# DAC.net
KiCad netlist of a schematic drawn in Altium Designer
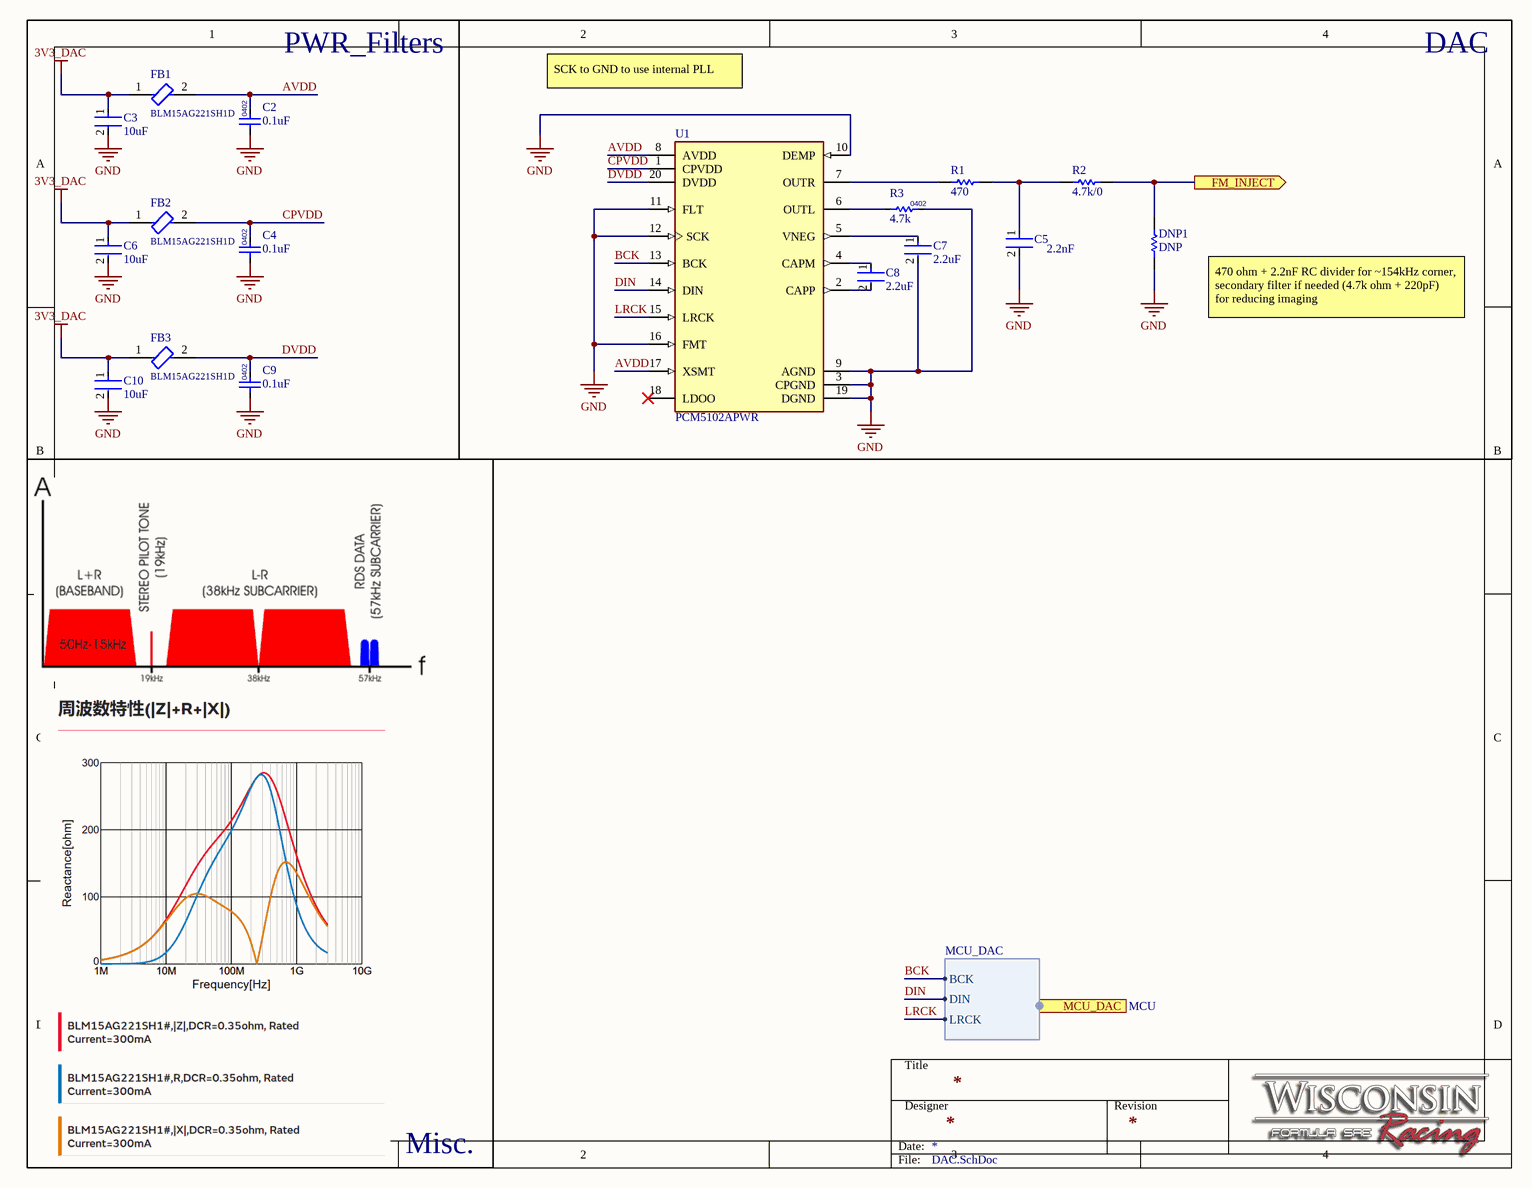
[diagram p0: DAC.SchDoc]

(export (version "E")
  (design (tool "Eeschema 10.0.6"))
  (components
    (comp (ref "C2")
      (value "0.1uF")
      (footprint "FP-CC0402-IPC_B")
      (fields (field (name "TOLERANCE") "10%"))
      (libsource (lib "University of Wisconsin Formula FSAE") (part "0402 ceramic cap"))
    )
    (comp (ref "C3")
      (value "10uF")
      (footprint "FP-GRM155-0_2-IPC_A")
      (description "Chip Multilayer Ceramic Capacitors for General Purpose, 0402, 10uF, X5R, 15%, 20%, 6.3V")
      (libsource (lib "Altium Content Vault") (part "b4654b650e69147ec39a6b967a45e02"))
    )
    (comp (ref "C4")
      (value "0.1uF")
      (footprint "FP-CC0402-IPC_B")
      (fields (field (name "TOLERANCE") "10%"))
      (libsource (lib "University of Wisconsin Formula FSAE") (part "0402 ceramic cap"))
    )
    (comp (ref "C5")
      (value "2.2nF")
      (footprint "FP-GRM155-0_05-IPC_C")
      (description "Chip Multilayer Ceramic Capacitors for General Purpose, 0402, 2200pF, C0G, 30ppm/°C, 5%, 50V")
      (libsource (lib "Altium Content Vault") (part "02cd4be3c70576c341d710602a673aa"))
    )
    (comp (ref "C6")
      (value "10uF")
      (footprint "FP-GRM155-0_2-IPC_A")
      (description "Chip Multilayer Ceramic Capacitors for General Purpose, 0402, 10uF, X5R, 15%, 20%, 6.3V")
      (libsource (lib "Altium Content Vault") (part "b4654b650e69147ec39a6b967a45e02"))
    )
    (comp (ref "C7")
      (value "2.2uF")
      (footprint "FP-GRM155-0_2-IPC_B")
      (description "Chip Multilayer Ceramic Capacitors for General Purpose, 0402, 2.2uF, X7R, 15%, 10%, 10V")
      (libsource (lib "Altium Content Vault") (part "b4654b650e69147ec39a6b967a45e02"))
    )
    (comp (ref "C8")
      (value "2.2uF")
      (footprint "FP-GRM155-0_2-IPC_B")
      (description "Chip Multilayer Ceramic Capacitors for General Purpose, 0402, 2.2uF, X7R, 15%, 10%, 10V")
      (libsource (lib "Altium Content Vault") (part "b4654b650e69147ec39a6b967a45e02"))
    )
    (comp (ref "C9")
      (value "0.1uF")
      (footprint "FP-CC0402-IPC_B")
      (fields (field (name "TOLERANCE") "10%"))
      (libsource (lib "University of Wisconsin Formula FSAE") (part "0402 ceramic cap"))
    )
    (comp (ref "C10")
      (value "10uF")
      (footprint "FP-GRM155-0_2-IPC_A")
      (description "Chip Multilayer Ceramic Capacitors for General Purpose, 0402, 10uF, X5R, 15%, 20%, 6.3V")
      (libsource (lib "Altium Content Vault") (part "b4654b650e69147ec39a6b967a45e02"))
    )
    (comp (ref "DNP1")
      (value "DNP")
      (footprint "RESC1005X40X25NL05T10")
      (fields (field (name "MANUFACTURER") "Yageo / Phycomp") (field (name "PART NUMBER") "RC0402JR-070RL"))
      (libsource (lib "Altium Content Vault") (part "RES"))
    )
    (comp (ref "FB1")
      (value "BLM15AG221SH1D")
      (footprint "FP-BLM15-0_05-MFG")
      (description "Chip Ferrite Bead, 0402, 220Ω @ 100MHz, 0.35Ω, 25%, 300mA")
      (fields (field (name "TOLERANCE") "25%"))
      (libsource (lib "Altium Content Vault") (part "5f30dd21d616792df468990f7003faa"))
    )
    (comp (ref "FB2")
      (value "BLM15AG221SH1D")
      (footprint "FP-BLM15-0_05-MFG")
      (description "Chip Ferrite Bead, 0402, 220Ω @ 100MHz, 0.35Ω, 25%, 300mA")
      (fields (field (name "TOLERANCE") "25%"))
      (libsource (lib "Altium Content Vault") (part "5f30dd21d616792df468990f7003faa"))
    )
    (comp (ref "FB3")
      (value "BLM15AG221SH1D")
      (footprint "FP-BLM15-0_05-MFG")
      (description "Chip Ferrite Bead, 0402, 220Ω @ 100MHz, 0.35Ω, 25%, 300mA")
      (fields (field (name "TOLERANCE") "25%"))
      (libsource (lib "Altium Content Vault") (part "5f30dd21d616792df468990f7003faa"))
    )
    (comp (ref "R1")
      (value "470")
      (footprint "RESC1005X40X25ML05T10")
      (fields (field (name "PART NUMBER") "RC0402FR-07470RL") (field (name "MANUFACTURER") "Yageo / Phycomp"))
      (libsource (lib "Altium Content Vault") (part "RES"))
    )
    (comp (ref "R2")
      (value "4.7k/0")
      (footprint "RESC1005X40X25NL05T10")
      (fields (field (name "MANUFACTURER") "Yageo / Phycomp") (field (name "PART NUMBER") "RC0402JR-070RL"))
      (libsource (lib "Altium Content Vault") (part "RES"))
    )
    (comp (ref "R3")
      (value "4.7k")
      (footprint "RESC1005X40X25NL05T10")
      (description "Res General Purpose Thick Film 0402 4.7K Ohm 1% 1/16W ±100ppm/°C Molded SMD Paper T/R")
      (fields (field (name "TOLERANCE") "1%") (field (name "Comment") "4.7k 1%"))
      (libsource (lib "University of Wisconsin Formula FSAE") (part "RES"))
    )
    (comp (ref "U1")
      (value "PCM5102APWR")
      (footprint "FP-PW0020A-IPC_A")
      (description "IC DAC 16/24/32BIT 384K 20TSSOP")
      (libsource (lib "Altium Content Vault") (part "831166dc95f78e7a0e4986cce343839"))
    )
  )
  (nets
    (net (code "2") (name "/AVDD") (class "Default")
      (node (ref "C2") (pin "2") (pinfunction "2_2") (pintype "passive"))
      (node (ref "FB1") (pin "2") (pinfunction "2_2") (pintype "passive"))
      (node (ref "U1") (pin "17") (pinfunction "XSMT_17") (pintype "input"))
      (node (ref "U1") (pin "8") (pinfunction "AVDD_8") (pintype "power_in"))
    )
    (net (code "3") (name "/BCK") (class "Default")
      (node (ref "U1") (pin "13") (pinfunction "BCK_13") (pintype "input"))
    )
    (net (code "4") (name "/CPVDD") (class "Default")
      (node (ref "C4") (pin "2") (pinfunction "2_2") (pintype "passive"))
      (node (ref "FB2") (pin "2") (pinfunction "2_2") (pintype "passive"))
      (node (ref "U1") (pin "1") (pinfunction "CPVDD_1") (pintype "power_in"))
    )
    (net (code "5") (name "/DIN") (class "Default")
      (node (ref "U1") (pin "14") (pinfunction "DIN_14") (pintype "input"))
    )
    (net (code "6") (name "/DVDD") (class "Default")
      (node (ref "C9") (pin "2") (pinfunction "2_2") (pintype "passive"))
      (node (ref "FB3") (pin "2") (pinfunction "2_2") (pintype "passive"))
      (node (ref "U1") (pin "20") (pinfunction "DVDD_20") (pintype "power_in"))
    )
    (net (code "7") (name "/FM_INJECT") (class "Default")
      (node (ref "DNP1") (pin "2") (pinfunction "2_2") (pintype "passive"))
      (node (ref "R2") (pin "2") (pinfunction "2_2") (pintype "passive"))
    )
    (net (code "8") (name "/LRCK") (class "Default")
      (node (ref "U1") (pin "15") (pinfunction "LRCK_15") (pintype "input"))
    )
    (net (code "10") (name "3V3_DAC") (class "Default")
      (node (ref "C10") (pin "1") (pinfunction "1_1") (pintype "passive"))
      (node (ref "C3") (pin "1") (pinfunction "1_1") (pintype "passive"))
      (node (ref "C6") (pin "1") (pinfunction "1_1") (pintype "passive"))
      (node (ref "FB1") (pin "1") (pinfunction "1_1") (pintype "passive"))
      (node (ref "FB2") (pin "1") (pinfunction "1_1") (pintype "passive"))
      (node (ref "FB3") (pin "1") (pinfunction "1_1") (pintype "passive"))
    )
    (net (code "11") (name "GND") (class "Default")
      (node (ref "C10") (pin "2") (pinfunction "2_2") (pintype "passive"))
      (node (ref "C2") (pin "1") (pinfunction "1_1") (pintype "passive"))
      (node (ref "C3") (pin "2") (pinfunction "2_2") (pintype "passive"))
      (node (ref "C4") (pin "1") (pinfunction "1_1") (pintype "passive"))
      (node (ref "C5") (pin "2") (pinfunction "2_2") (pintype "passive"))
      (node (ref "C6") (pin "2") (pinfunction "2_2") (pintype "passive"))
      (node (ref "C7") (pin "2") (pinfunction "2_2") (pintype "passive"))
      (node (ref "C9") (pin "1") (pinfunction "1_1") (pintype "passive"))
      (node (ref "DNP1") (pin "1") (pinfunction "1_1") (pintype "passive"))
      (node (ref "R3") (pin "2") (pinfunction "2_2") (pintype "passive"))
      (node (ref "U1") (pin "10") (pinfunction "DEMP_10") (pintype "input"))
      (node (ref "U1") (pin "11") (pinfunction "FLT_11") (pintype "input"))
      (node (ref "U1") (pin "12") (pinfunction "SCK_12") (pintype "input"))
      (node (ref "U1") (pin "16") (pinfunction "FMT_16") (pintype "input"))
      (node (ref "U1") (pin "19") (pinfunction "DGND_19") (pintype "power_in"))
      (node (ref "U1") (pin "3") (pinfunction "CPGND_3") (pintype "power_in"))
      (node (ref "U1") (pin "9") (pinfunction "AGND_9") (pintype "power_in"))
    )
    (net (code "12") (name "Net-(C5-Pad1)") (class "Default")
      (node (ref "C5") (pin "1") (pinfunction "1_1") (pintype "passive"))
      (node (ref "R1") (pin "2") (pinfunction "2_2") (pintype "passive"))
      (node (ref "R2") (pin "1") (pinfunction "1_1") (pintype "passive"))
    )
    (net (code "13") (name "Net-(U1-CAPM)") (class "Default")
      (node (ref "C8") (pin "1") (pinfunction "1_1") (pintype "passive"))
      (node (ref "U1") (pin "4") (pinfunction "CAPM_4") (pintype "output"))
    )
    (net (code "14") (name "Net-(U1-CAPP)") (class "Default")
      (node (ref "C8") (pin "2") (pinfunction "2_2") (pintype "passive"))
      (node (ref "U1") (pin "2") (pinfunction "CAPP_2") (pintype "output"))
    )
    (net (code "15") (name "Net-(U1-OUTL)") (class "Default")
      (node (ref "R3") (pin "1") (pinfunction "1_1") (pintype "passive"))
      (node (ref "U1") (pin "6") (pinfunction "OUTL_6") (pintype "passive"))
    )
    (net (code "16") (name "Net-(U1-OUTR)") (class "Default")
      (node (ref "R1") (pin "1") (pinfunction "1_1") (pintype "passive"))
      (node (ref "U1") (pin "7") (pinfunction "OUTR_7") (pintype "passive"))
    )
    (net (code "17") (name "Net-(U1-VNEG)") (class "Default")
      (node (ref "C7") (pin "1") (pinfunction "1_1") (pintype "passive"))
      (node (ref "U1") (pin "5") (pinfunction "VNEG_5") (pintype "output"))
    )
    (net (code "18") (name "unconnected-(U1-LDOO-Pad18)") (class "Default")
      (node (ref "U1") (pin "18") (pinfunction "LDOO_18") (pintype "power_in+no_connect"))
    )
  )
)
